# OperantFED.net
KiCad netlist of a schematic drawn in EAGLE
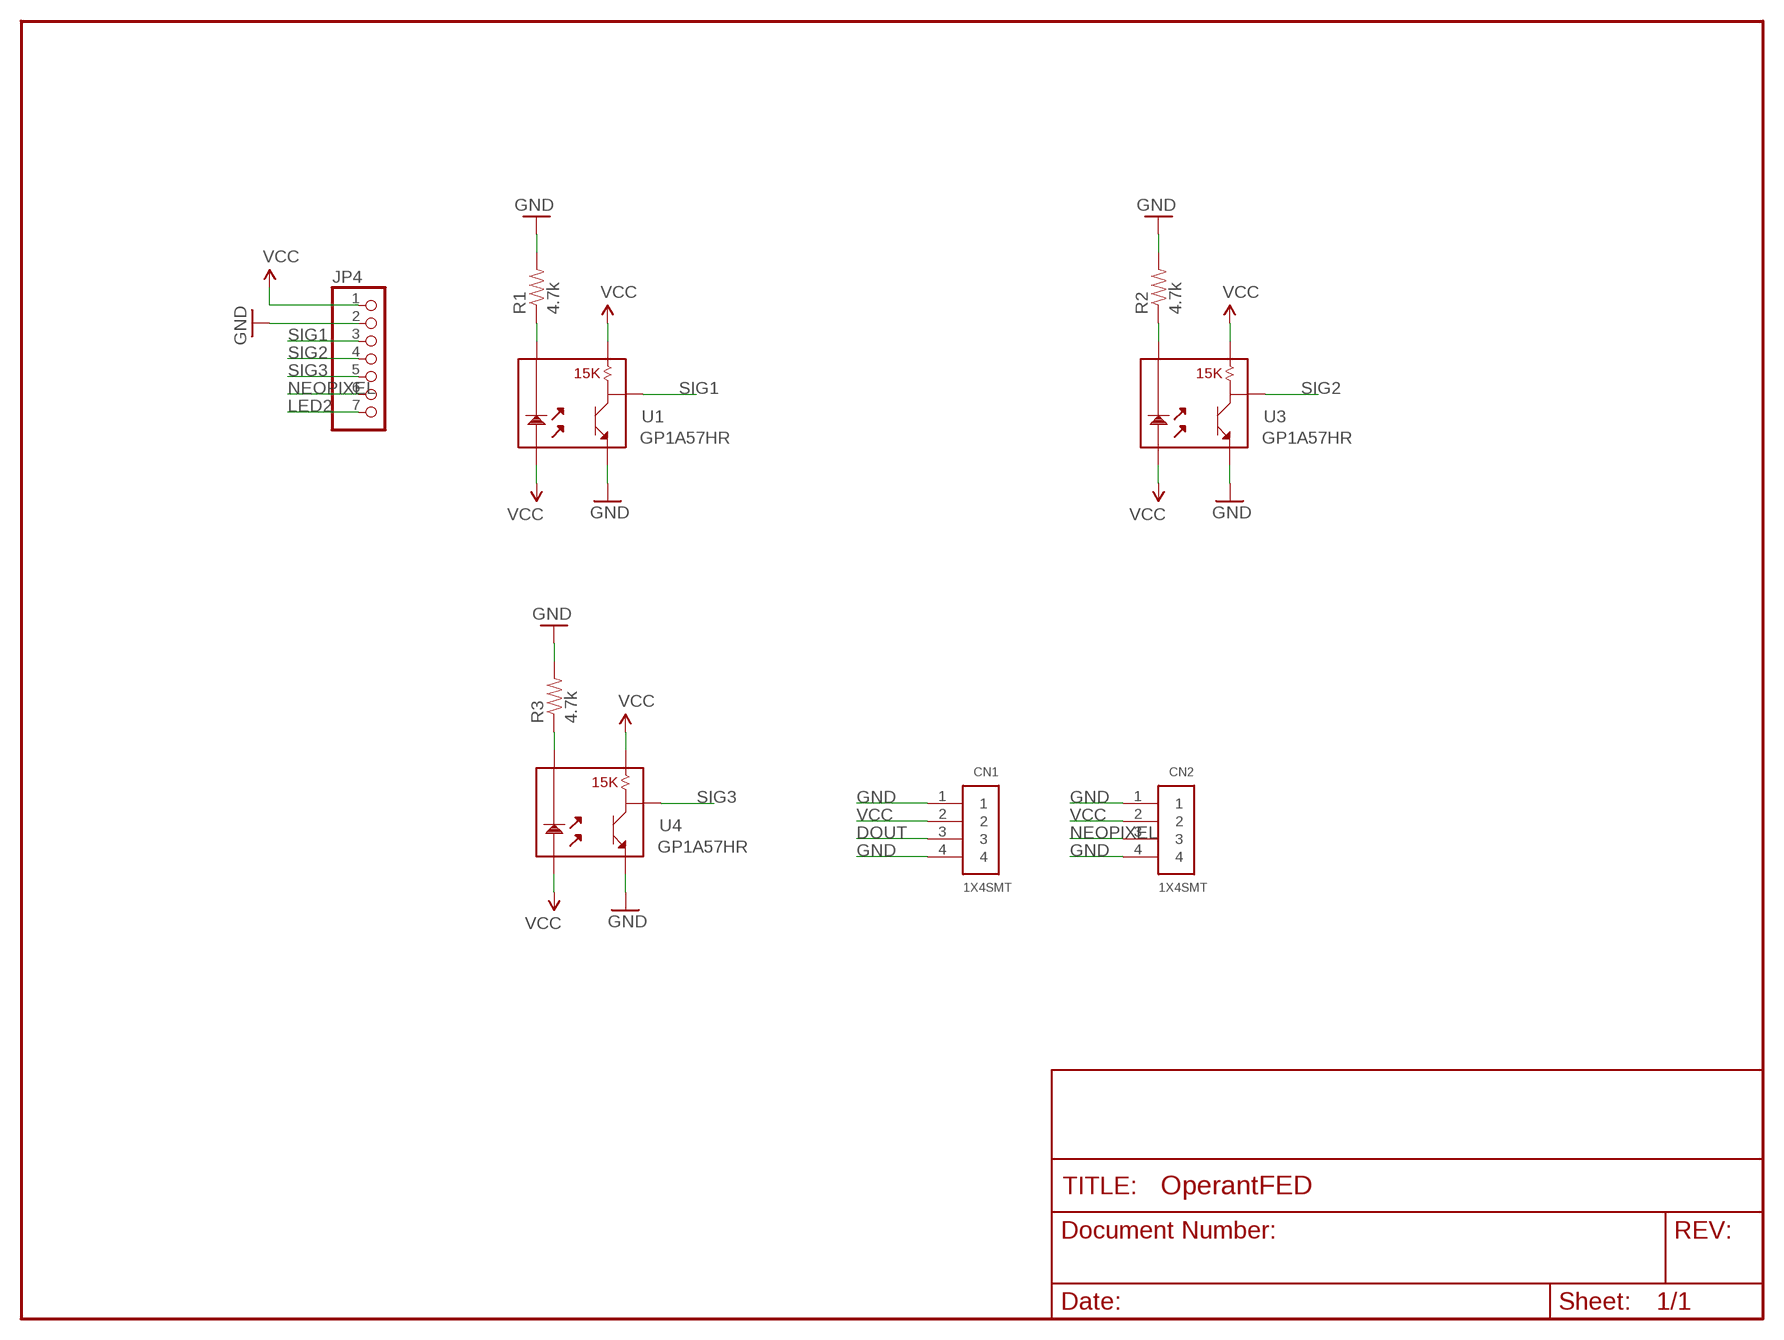
[diagram p0: schematic, sheet 1]

(export (version "E")
  (design (tool "Eeschema 10.0.6"))
  (components
    (comp (ref "CN1")
      (value "1X4SMT")
      (footprint "eagle-import:1X4-SMT")
      (libsource (lib "eagle-import") (part "1X4SMT"))
    )
    (comp (ref "CN2")
      (value "1X4SMT")
      (footprint "eagle-import:1X4-SMT")
      (libsource (lib "eagle-import") (part "1X4SMT"))
    )
    (comp (ref "JP4")
      (value "PINHD-1X7")
      (footprint "eagle-import:1X07")
      (libsource (lib "eagle-import") (part "PINHD-1X7"))
    )
    (comp (ref "R1")
      (value "4.7k")
      (footprint "eagle-import:AXIAL-0.3")
      (libsource (lib "eagle-import") (part "RESISTORPTH1"))
    )
    (comp (ref "R2")
      (value "4.7k")
      (footprint "eagle-import:AXIAL-0.3")
      (libsource (lib "eagle-import") (part "RESISTORPTH1"))
    )
    (comp (ref "R3")
      (value "4.7k")
      (footprint "eagle-import:AXIAL-0.3")
      (libsource (lib "eagle-import") (part "RESISTORPTH1"))
    )
    (comp (ref "U1")
      (value "GP1A57HR")
      (footprint "eagle-import:GP1A57HR")
      (libsource (lib "eagle-import") (part "GP1A57HR"))
    )
    (comp (ref "U3")
      (value "GP1A57HR")
      (footprint "eagle-import:GP1A57HR")
      (libsource (lib "eagle-import") (part "GP1A57HR"))
    )
    (comp (ref "U4")
      (value "GP1A57HR")
      (footprint "eagle-import:GP1A57HR")
      (libsource (lib "eagle-import") (part "GP1A57HR"))
    )
  )
  (nets
    (net (code "1") (name "/DOUT") (class "Default")
      (node (ref "CN1") (pin "3") (pinfunction "3_3") (pintype "bidirectional"))
    )
    (net (code "2") (name "/LED2") (class "Default")
      (node (ref "JP4") (pin "7") (pinfunction "7_7") (pintype "passive"))
    )
    (net (code "3") (name "/NEOPIXEL") (class "Default")
      (node (ref "CN2") (pin "3") (pinfunction "3_3") (pintype "bidirectional"))
      (node (ref "JP4") (pin "6") (pinfunction "6_6") (pintype "passive"))
    )
    (net (code "4") (name "/SIG1") (class "Default")
      (node (ref "JP4") (pin "3") (pinfunction "3_3") (pintype "passive"))
      (node (ref "U1") (pin "4") (pinfunction "4_4") (pintype "bidirectional"))
    )
    (net (code "5") (name "/SIG2") (class "Default")
      (node (ref "JP4") (pin "4") (pinfunction "4_4") (pintype "passive"))
      (node (ref "U3") (pin "4") (pinfunction "4_4") (pintype "bidirectional"))
    )
    (net (code "6") (name "/SIG3") (class "Default")
      (node (ref "JP4") (pin "5") (pinfunction "5_5") (pintype "passive"))
      (node (ref "U4") (pin "4") (pinfunction "4_4") (pintype "bidirectional"))
    )
    (net (code "7") (name "GND") (class "Default")
      (node (ref "CN1") (pin "1") (pinfunction "1_1") (pintype "bidirectional"))
      (node (ref "CN1") (pin "4") (pinfunction "4_4") (pintype "bidirectional"))
      (node (ref "CN2") (pin "1") (pinfunction "1_1") (pintype "bidirectional"))
      (node (ref "CN2") (pin "4") (pinfunction "4_4") (pintype "bidirectional"))
      (node (ref "JP4") (pin "2") (pinfunction "2_2") (pintype "passive"))
      (node (ref "R1") (pin "P$2") (pinfunction "2_P$2") (pintype "passive"))
      (node (ref "R2") (pin "P$2") (pinfunction "2_P$2") (pintype "passive"))
      (node (ref "R3") (pin "P$2") (pinfunction "2_P$2") (pintype "passive"))
      (node (ref "U1") (pin "5") (pinfunction "5_5") (pintype "bidirectional"))
      (node (ref "U3") (pin "5") (pinfunction "5_5") (pintype "bidirectional"))
      (node (ref "U4") (pin "5") (pinfunction "5_5") (pintype "bidirectional"))
    )
    (net (code "8") (name "Net-(R1-1)") (class "Default")
      (node (ref "R1") (pin "P$1") (pinfunction "1_P$1") (pintype "passive"))
      (node (ref "U1") (pin "2") (pinfunction "2_2") (pintype "bidirectional"))
    )
    (net (code "9") (name "Net-(R2-1)") (class "Default")
      (node (ref "R2") (pin "P$1") (pinfunction "1_P$1") (pintype "passive"))
      (node (ref "U3") (pin "2") (pinfunction "2_2") (pintype "bidirectional"))
    )
    (net (code "10") (name "Net-(R3-1)") (class "Default")
      (node (ref "R3") (pin "P$1") (pinfunction "1_P$1") (pintype "passive"))
      (node (ref "U4") (pin "2") (pinfunction "2_2") (pintype "bidirectional"))
    )
    (net (code "11") (name "VCC") (class "Default")
      (node (ref "CN1") (pin "2") (pinfunction "2_2") (pintype "bidirectional"))
      (node (ref "CN2") (pin "2") (pinfunction "2_2") (pintype "bidirectional"))
      (node (ref "JP4") (pin "1") (pinfunction "1_1") (pintype "passive"))
      (node (ref "U1") (pin "1") (pinfunction "1_1") (pintype "bidirectional"))
      (node (ref "U1") (pin "3") (pinfunction "3_3") (pintype "bidirectional"))
      (node (ref "U3") (pin "1") (pinfunction "1_1") (pintype "bidirectional"))
      (node (ref "U3") (pin "3") (pinfunction "3_3") (pintype "bidirectional"))
      (node (ref "U4") (pin "1") (pinfunction "1_1") (pintype "bidirectional"))
      (node (ref "U4") (pin "3") (pinfunction "3_3") (pintype "bidirectional"))
    )
  )
)
